# mains_relay.net
KiCad netlist of a schematic drawn in EAGLE
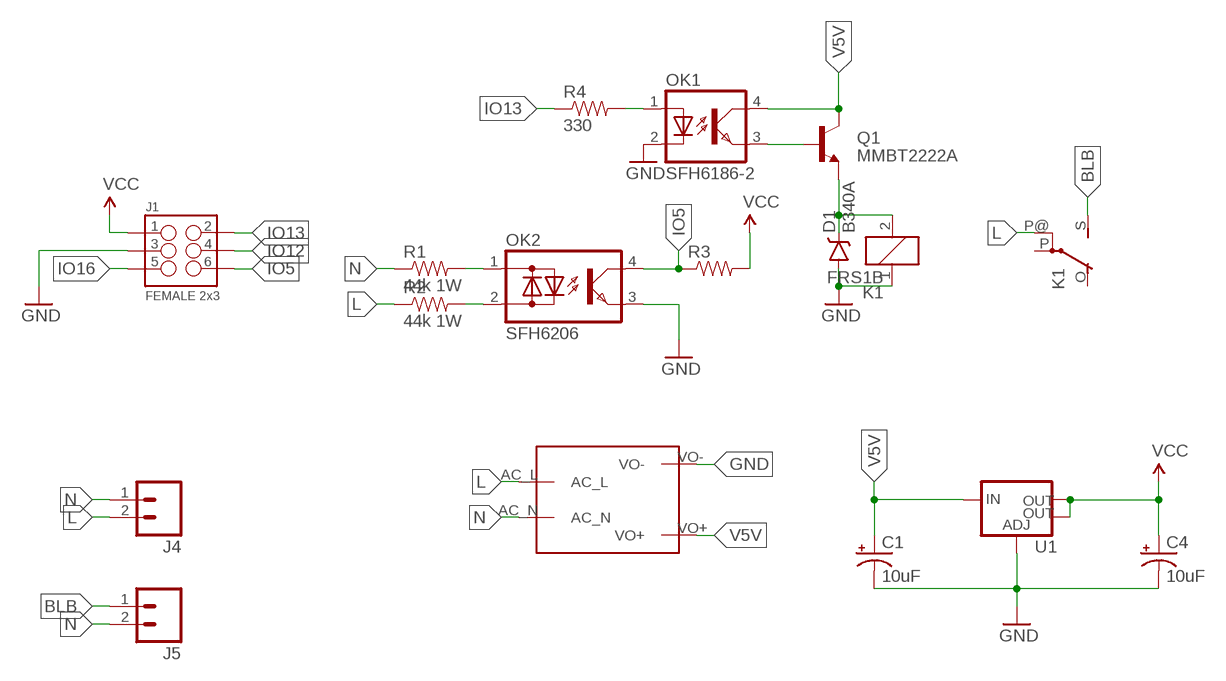
[diagram p0: schematic, sheet 1]

(export (version "E")
  (design (tool "Eeschema 10.0.6"))
  (components
    (comp (ref "C1")
      (value "10uF")
      (footprint "eagle-import:EIA3216-KIT")
      (libsource (lib "eagle-import") (part "CAP_POL1206-KIT"))
    )
    (comp (ref "C4")
      (value "10uF")
      (footprint "eagle-import:EIA3216-KIT")
      (libsource (lib "eagle-import") (part "CAP_POL1206-KIT"))
    )
    (comp (ref "D1")
      (value "B340A")
      (footprint "eagle-import:SMA-DIODE")
      (libsource (lib "eagle-import") (part "DIODE-SCHOTTKY-B340A"))
    )
    (comp (ref "J1")
      (value "FEMALE 2x3")
      (footprint "eagle-import:2X3-SHROUDED")
      (libsource (lib "eagle-import") (part "M03X2SHROUD"))
    )
    (comp (ref "J4")
      (value "M025MM")
      (footprint "eagle-import:SCREWTERMINAL-5MM-2")
      (libsource (lib "eagle-import") (part "M025MM"))
    )
    (comp (ref "J5")
      (value "M025MM")
      (footprint "eagle-import:SCREWTERMINAL-5MM-2")
      (libsource (lib "eagle-import") (part "M025MM"))
    )
    (comp (ref "K1")
      (value "FRS1B")
      (footprint "eagle-import:FRS1B")
      (libsource (lib "eagle-import") (part "FRS1B"))
    )
    (comp (ref "OK1")
      (value "SFH6186-2")
      (footprint "eagle-import:SMD4")
      (libsource (lib "eagle-import") (part "SFH618?6-2"))
    )
    (comp (ref "OK2")
      (value "SFH6206")
      (footprint "eagle-import:DIL4-SMD")
      (libsource (lib "eagle-import") (part "SFH6206"))
    )
    (comp (ref "Q1")
      (value "MMBT2222A")
      (footprint "eagle-import:SOT23-3")
      (libsource (lib "eagle-import") (part "TRANSISTOR_NPNMMBT2222A"))
    )
    (comp (ref "R1")
      (value "44k 1W")
      (footprint "eagle-import:AXIAL-0.4")
      (libsource (lib "eagle-import") (part "SparkFun-Resistors_RESISTORPTH-1/4W"))
    )
    (comp (ref "R2")
      (value "44k 1W")
      (footprint "eagle-import:AXIAL-0.4")
      (libsource (lib "eagle-import") (part "SparkFun-Resistors_RESISTORPTH-1/4W"))
    )
    (comp (ref "R3")
      (value "RESISTOR0805-RES")
      (footprint "eagle-import:0805")
      (libsource (lib "eagle-import") (part "RESISTOR0805-RES"))
    )
    (comp (ref "R4")
      (value "330")
      (footprint "eagle-import:0805")
      (libsource (lib "eagle-import") (part "RESISTOR0805-RES"))
    )
    (comp (ref "U$1")
      (value "MAINS_CONVERTERS")
      (footprint "eagle-import:HLK-PM01")
      (libsource (lib "eagle-import") (part "MAINS_CONVERTERS"))
    )
    (comp (ref "U1")
      (value "V_REG_LM1117SOT223")
      (footprint "eagle-import:SOT223")
      (libsource (lib "eagle-import") (part "V_REG_LM1117SOT223"))
    )
  )
  (nets
    (net (code "1") (name "BLB") (class "Default")
      (node (ref "J5") (pin "1") (pinfunction "1_1") (pintype "passive"))
      (node (ref "K1") (pin "S") (pinfunction "S_S") (pintype "passive"))
    )
    (net (code "2") (name "GND") (class "Default")
      (node (ref "C1") (pin "C") (pinfunction "-_C") (pintype "passive"))
      (node (ref "C4") (pin "C") (pinfunction "-_C") (pintype "passive"))
      (node (ref "D1") (pin "A") (pinfunction "A_A") (pintype "passive"))
      (node (ref "J1") (pin "3") (pinfunction "3_3") (pintype "bidirectional"))
      (node (ref "K1") (pin "1") (pinfunction "1_1") (pintype "passive"))
      (node (ref "OK1") (pin "2") (pinfunction "C_2") (pintype "passive"))
      (node (ref "OK2") (pin "3") (pinfunction "E_3") (pintype "passive"))
      (node (ref "U$1") (pin "VO-") (pinfunction "VO-_VO-") (pintype "output"))
      (node (ref "U1") (pin "1") (pinfunction "ADJ_1") (pintype "input"))
    )
    (net (code "3") (name "IO5") (class "Default")
      (node (ref "J1") (pin "6") (pinfunction "6_6") (pintype "bidirectional"))
      (node (ref "OK2") (pin "4") (pinfunction "C_4") (pintype "passive"))
      (node (ref "R3") (pin "1") (pinfunction "1_1") (pintype "passive"))
    )
    (net (code "4") (name "IO12") (class "Default")
      (node (ref "J1") (pin "4") (pinfunction "4_4") (pintype "bidirectional"))
    )
    (net (code "5") (name "IO13") (class "Default")
      (node (ref "J1") (pin "2") (pinfunction "2_2") (pintype "bidirectional"))
      (node (ref "R4") (pin "1") (pinfunction "1_1") (pintype "passive"))
    )
    (net (code "6") (name "IO16") (class "Default")
      (node (ref "J1") (pin "5") (pinfunction "5_5") (pintype "bidirectional"))
    )
    (net (code "7") (name "L") (class "Default")
      (node (ref "J4") (pin "2") (pinfunction "2_2") (pintype "passive"))
      (node (ref "K1") (pin "P@") (pinfunction "P_P@") (pintype "passive"))
      (node (ref "R2") (pin "P$1") (pinfunction "1_P$1") (pintype "passive"))
      (node (ref "U$1") (pin "AC_L") (pinfunction "AC_L_AC_L") (pintype "input"))
    )
    (net (code "8") (name "N") (class "Default")
      (node (ref "J4") (pin "1") (pinfunction "1_1") (pintype "passive"))
      (node (ref "J5") (pin "2") (pinfunction "2_2") (pintype "passive"))
      (node (ref "R1") (pin "P$1") (pinfunction "1_P$1") (pintype "passive"))
      (node (ref "U$1") (pin "AC_N") (pinfunction "AC_N_AC_N") (pintype "input"))
    )
    (net (code "9") (name "Net-(OK1-A)") (class "Default")
      (node (ref "OK1") (pin "1") (pinfunction "A_1") (pintype "passive"))
      (node (ref "R4") (pin "2") (pinfunction "2_2") (pintype "passive"))
    )
    (net (code "10") (name "Net-(OK1-EMIT)") (class "Default")
      (node (ref "OK1") (pin "3") (pinfunction "EMIT_3") (pintype "passive"))
      (node (ref "Q1") (pin "1") (pinfunction "B_1") (pintype "passive"))
    )
    (net (code "11") (name "Net-(OK2-AC1)") (class "Default")
      (node (ref "OK2") (pin "1") (pinfunction "AC1_1") (pintype "passive"))
      (node (ref "R1") (pin "P$2") (pinfunction "2_P$2") (pintype "passive"))
    )
    (net (code "12") (name "Net-(OK2-AC2)") (class "Default")
      (node (ref "OK2") (pin "2") (pinfunction "AC2_2") (pintype "passive"))
      (node (ref "R2") (pin "P$2") (pinfunction "2_P$2") (pintype "passive"))
    )
    (net (code "13") (name "Net-(Q1-E)") (class "Default")
      (node (ref "D1") (pin "C") (pinfunction "C_C") (pintype "passive"))
      (node (ref "K1") (pin "2") (pinfunction "2_2") (pintype "passive"))
      (node (ref "Q1") (pin "2") (pinfunction "E_2") (pintype "passive"))
    )
    (net (code "14") (name "V5V") (class "Default")
      (node (ref "C1") (pin "A") (pinfunction "+_A") (pintype "passive"))
      (node (ref "OK1") (pin "4") (pinfunction "COL_4") (pintype "passive"))
      (node (ref "Q1") (pin "3") (pinfunction "C_3") (pintype "passive"))
      (node (ref "U$1") (pin "VO+") (pinfunction "VO+_VO+") (pintype "output"))
      (node (ref "U1") (pin "3") (pinfunction "IN_3") (pintype "input"))
    )
    (net (code "15") (name "VCC") (class "Default")
      (node (ref "C4") (pin "A") (pinfunction "+_A") (pintype "passive"))
      (node (ref "J1") (pin "1") (pinfunction "1_1") (pintype "bidirectional"))
      (node (ref "R3") (pin "2") (pinfunction "2_2") (pintype "passive"))
      (node (ref "U1") (pin "2") (pinfunction "OUT_2") (pintype "output"))
      (node (ref "U1") (pin "4") (pinfunction "OUT_4") (pintype "output"))
    )
    (net (code "16") (name "unconnected-(K1-PadO)") (class "Default")
      (node (ref "K1") (pin "O") (pinfunction "O_O") (pintype "passive"))
    )
    (net (code "17") (name "unconnected-(K1-PadP)") (class "Default")
      (node (ref "K1") (pin "P") (pinfunction "P_P") (pintype "passive"))
    )
  )
)
